# BSPD_-.net
KiCad netlist of a schematic drawn in EasyEDA Pro
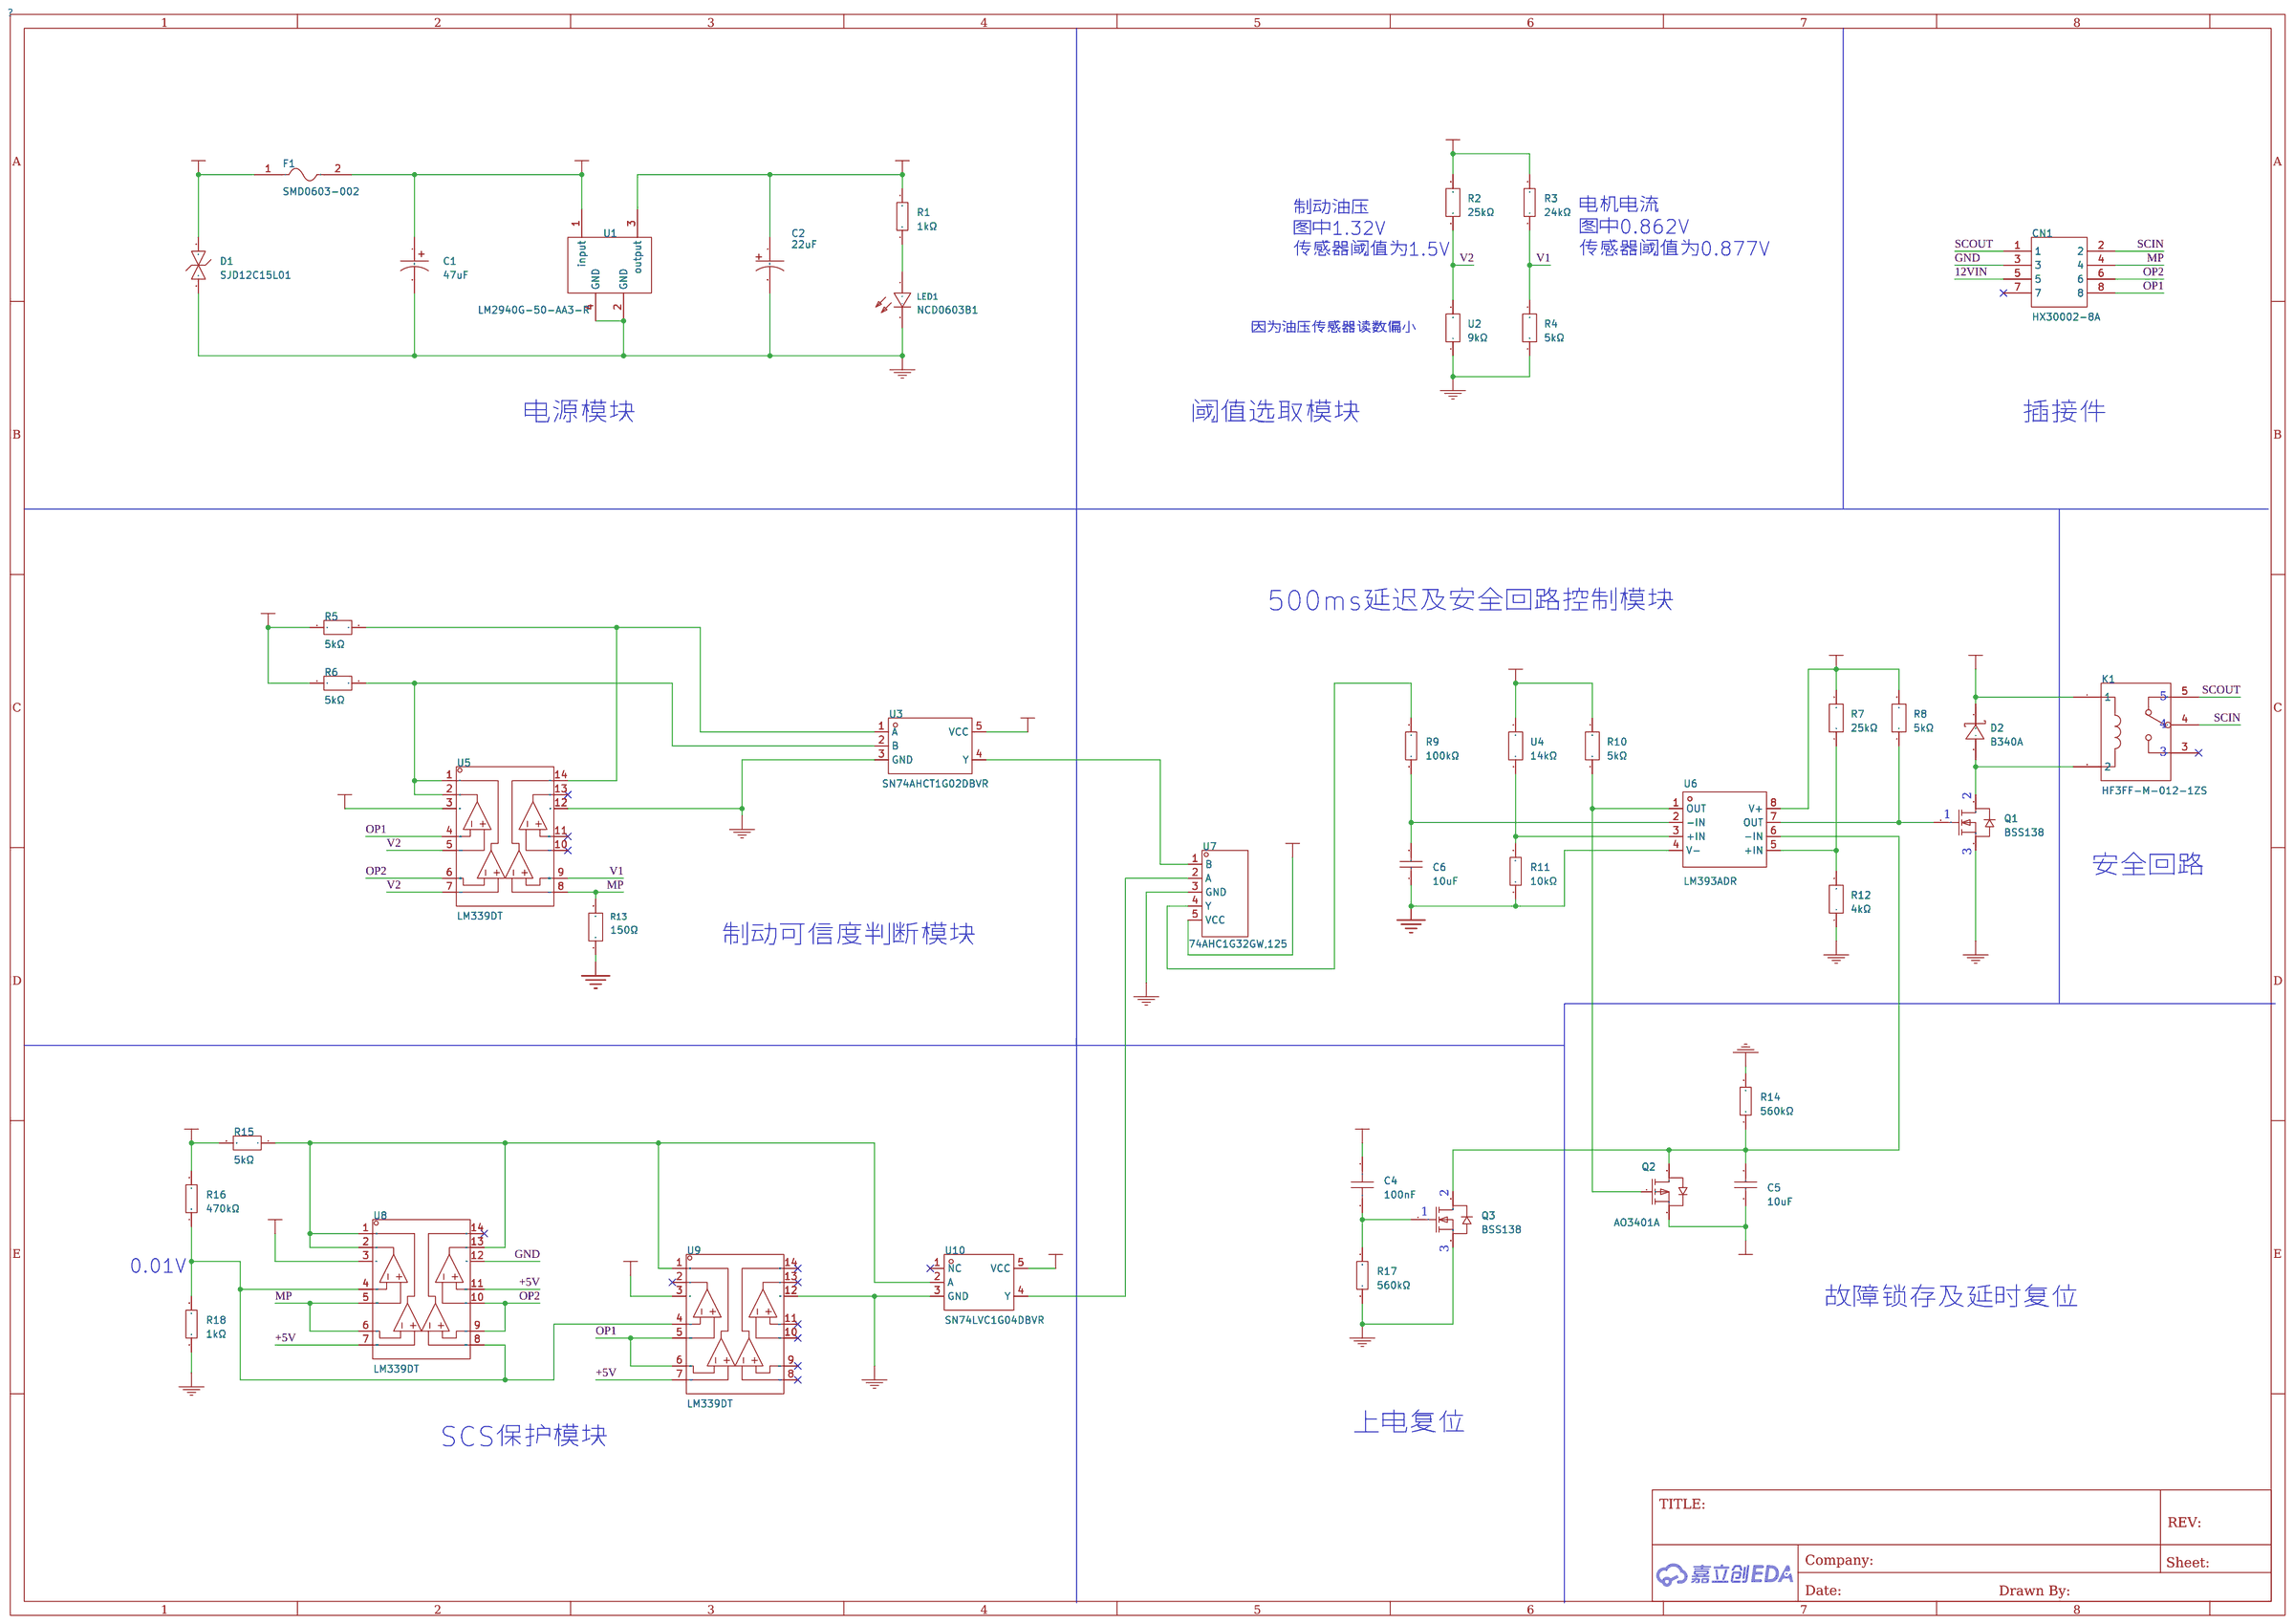
[diagram p0: schematic sheet]

(export (version "E")
  (design (tool "Eeschema 10.0.6"))
  (components
    (comp (ref "C1")
      (value "47uF")
      (footprint "easyedapro:CAP-SMD_BD8.0-L8.3-W8.3-FD")
      (description "容值:47uF;精度:±20%;额定电压:63V;")
      (fields (field (name "Manufacturer Part") "HBW470M1JTR-0810") (field (name "Manufacturer") "lelon(立隆)"))
      (libsource (lib "easyedapro") (part "HBW470M1JTR-0810"))
    )
    (comp (ref "C2")
      (value "22uF")
      (footprint "easyedapro:CAP-SMD_BD6.3-L6.6-W6.6-FD")
      (fields (field (name "Manufacturer Part") "EEHZA1J220XP") (field (name "Manufacturer") "PANASONIC(松下)"))
      (libsource (lib "easyedapro") (part "EEHZA1J220XP"))
    )
    (comp (ref "C4")
      (value "100nF")
      (footprint "easyedapro:C0603")
      (description "容值:100nF;精度:±10%;额定电压:50V;材质(温度系数):X7R;")
      (fields
        (field (name "Manufacturer Part") "CC0603KRX7R9BB104")
        (field (name "Manufacturer") "YAGEO(国巨)")
      )
      (libsource (lib "easyedapro") (part "CC0603KRX7R9BB104"))
    )
    (comp (ref "C5")
      (value "10uF")
      (footprint "easyedapro:C0805")
      (description "容值:10uF;精度:±10%;额定电压:25V;材质(温度系数):X5R;")
      (fields
        (field (name "Manufacturer Part") "CL21A106KAYNNNE")
        (field (name "Manufacturer") "SAMSUNG(三星)")
      )
      (libsource (lib "easyedapro") (part "CL21A106KAYNNNE"))
    )
    (comp (ref "C6")
      (value "10uF")
      (footprint "easyedapro:C0805")
      (description "容值:10uF;精度:±10%;额定电压:25V;材质(温度系数):X5R;")
      (fields
        (field (name "Manufacturer Part") "CL21A106KAYNNNE")
        (field (name "Manufacturer") "SAMSUNG(三星)")
      )
      (libsource (lib "easyedapro") (part "CL21A106KAYNNNE"))
    )
    (comp (ref "CN1")
      (value "HX30002-8A")
      (footprint "easyedapro:CONN-TH_30002-8A-T1P")
      (description "参考系列:-;间距:3mm;插针结构:2x4P;排数:2;每排PIN数:4;行距:3mm;安装方式:-;触头材质:黄铜;")
      (fields (field (name "Manufacturer") "HX(红星)"))
      (libsource (lib "easyedapro") (part "30002-8A-T1P"))
    )
    (comp (ref "D1")
      (value "SJD12C15L01")
      (footprint "easyedapro:SOD-123_L2.7-W1.6-LS3.7-BI")
      (description "反向截止电压(Vrwm):15V;击穿电压(VBR):16.7V;峰值脉冲电流(Ipp)@8/20us:8.2A;钳位电压(Vc)@Ipp:24.4V;")
      (fields (field (name "Manufacturer") "Brightking(君耀电子)"))
      (libsource (lib "easyedapro") (part "SJD12C15L01"))
    )
    (comp (ref "D2")
      (value "B340A")
      (footprint "easyedapro:SMA_L4.3-W2.6-LS5.1-RD")
      (description "直流反向耐压(Vr):40V;平均整流电流(Io):3A;正向压降(Vf):550mV@3A;")
      (fields (field (name "Manufacturer") "MDD"))
      (libsource (lib "easyedapro") (part "B340A"))
    )
    (comp (ref "F1")
      (value "SMD0603-002")
      (footprint "easyedapro:F0603")
      (description "30V,0.02A")
      (fields (field (name "Manufacturer") "台湾陆海"))
      (libsource (lib "easyedapro") (part "SMD0603-002"))
    )
    (comp (ref "K1")
      (value "HF3FF-M-012-1ZS")
      (footprint "easyedapro:RELAY-TH_HF3FF-XX-1ZXX-XXX")
      (description "引脚数:5;线圈电压:12V;触点形式:一组转换:1C(单刀双掷-转换);触点容量(电阻负载):-;触点材料:AgSnO2;")
      (fields (field (name "Manufacturer") "HF(宏发)"))
      (libsource (lib "easyedapro") (part "HF3FF-M-012-1ZS"))
    )
    (comp (ref "LED1")
      (value "NCD0603B1")
      (footprint "easyedapro:LED0603-RD")
      (description "发光颜色:蓝灯;")
      (fields (field (name "Manufacturer") "国星光电"))
      (libsource (lib "easyedapro") (part "FC-DA1608BK-470H10"))
    )
    (comp (ref "Q1")
      (value "BSS138")
      (footprint "easyedapro:SOT-23-3_L2.9-W1.3-P1.90-LS2.4-BR")
      (description "类型:N沟道;漏源电压(Vdss):50V;连续漏极电流(Id):220mA;功率(Pd):360mW;导通电阻(RDS(on)@Vgs,Id):3.5Ω@10V,220mA;")
      (fields (field (name "Manufacturer") "CJ(江苏长电/长晶)"))
      (libsource (lib "easyedapro") (part "BSS138"))
    )
    (comp (ref "Q2")
      (value "AO3401A")
      (footprint "easyedapro:SOT-23_L2.9-W1.3-P1.90-LS2.4-BR")
      (fields (field (name "Manufacturer") "UMW(广东友台半导体)"))
      (libsource (lib "easyedapro") (part "AO3401A_C347476"))
    )
    (comp (ref "Q3")
      (value "BSS138")
      (footprint "easyedapro:SOT-23-3_L2.9-W1.3-P1.90-LS2.4-BR")
      (description "类型:N沟道;漏源电压(Vdss):50V;连续漏极电流(Id):220mA;功率(Pd):360mW;导通电阻(RDS(on)@Vgs,Id):3.5Ω@10V,220mA;")
      (fields (field (name "Manufacturer") "CJ(江苏长电/长晶)"))
      (libsource (lib "easyedapro") (part "BSS138"))
    )
    (comp (ref "R1")
      (value "1kΩ")
      (footprint "easyedapro:R0603")
      (description "电阻类型:厚膜电阻;阻值:1kΩ;精度:±1%;功率:100mW;")
      (fields
        (field (name "Manufacturer Part") "0603WAF1001T5E")
        (field (name "Manufacturer") "UNI-ROYAL(厚声)")
      )
      (libsource (lib "easyedapro") (part "0603WAF1001T5E"))
    )
    (comp (ref "R2")
      (value "25kΩ")
      (footprint "easyedapro:R0603")
      (description "电阻类型:薄膜电阻;阻值:25kΩ;精度:±0.1%;功率:100mW;")
      (fields (field (name "Manufacturer Part") "AR03BTCX2502") (field (name "Manufacturer") "Viking(光颉)"))
      (libsource (lib "easyedapro") (part "AR03BTCX2502"))
    )
    (comp (ref "R3")
      (value "24kΩ")
      (footprint "easyedapro:R0603")
      (description "电阻类型:厚膜电阻;阻值:24kΩ;精度:±1%;功率:100mW;温度系数:±100ppm/°C;")
      (fields
        (field (name "Manufacturer Part") "0603WAF2402T5E")
        (field (name "Manufacturer") "UNI-ROYAL(厚声)")
      )
      (libsource (lib "easyedapro") (part "0603WAF2402T5E"))
    )
    (comp (ref "R4")
      (value "5kΩ")
      (footprint "easyedapro:R0603")
      (description "电阻类型:薄膜电阻;阻值:5kΩ;精度:±0.1%;功率:100mW;")
      (fields (field (name "Manufacturer Part") "AR03BTCX5001") (field (name "Manufacturer") "Viking(光颉)"))
      (libsource (lib "easyedapro") (part "AR03BTCX5001"))
    )
    (comp (ref "R5")
      (value "5kΩ")
      (footprint "easyedapro:R0603")
      (description "电阻类型:薄膜电阻;阻值:5kΩ;精度:±0.1%;功率:100mW;")
      (fields (field (name "Manufacturer Part") "AR03BTCX5001") (field (name "Manufacturer") "Viking(光颉)"))
      (libsource (lib "easyedapro") (part "AR03BTCX5001"))
    )
    (comp (ref "R6")
      (value "5kΩ")
      (footprint "easyedapro:R0603")
      (description "电阻类型:薄膜电阻;阻值:5kΩ;精度:±0.1%;功率:100mW;")
      (fields (field (name "Manufacturer Part") "AR03BTCX5001") (field (name "Manufacturer") "Viking(光颉)"))
      (libsource (lib "easyedapro") (part "AR03BTCX5001"))
    )
    (comp (ref "R7")
      (value "25kΩ")
      (footprint "easyedapro:R0603")
      (description "电阻类型:薄膜电阻;阻值:25kΩ;精度:±0.1%;功率:100mW;")
      (fields (field (name "Manufacturer Part") "AR03BTCX2502") (field (name "Manufacturer") "Viking(光颉)"))
      (libsource (lib "easyedapro") (part "AR03BTCX2502"))
    )
    (comp (ref "R8")
      (value "5kΩ")
      (footprint "easyedapro:R0603")
      (description "电阻类型:薄膜电阻;阻值:5kΩ;精度:±0.1%;功率:100mW;")
      (fields (field (name "Manufacturer Part") "AR03BTCX5001") (field (name "Manufacturer") "Viking(光颉)"))
      (libsource (lib "easyedapro") (part "AR03BTCX5001"))
    )
    (comp (ref "R9")
      (value "100kΩ")
      (footprint "easyedapro:R0603")
      (description "电阻类型:厚膜电阻;阻值:100kΩ;精度:±1%;功率:100mW;")
      (fields
        (field (name "Manufacturer Part") "0603WAF1003T5E")
        (field (name "Manufacturer") "UNI-ROYAL(厚声)")
      )
      (libsource (lib "easyedapro") (part "0603WAF1003T5E"))
    )
    (comp (ref "R10")
      (value "5kΩ")
      (footprint "easyedapro:R0603")
      (description "电阻类型:薄膜电阻;阻值:5kΩ;精度:±0.1%;功率:100mW;")
      (fields (field (name "Manufacturer Part") "AR03BTCX5001") (field (name "Manufacturer") "Viking(光颉)"))
      (libsource (lib "easyedapro") (part "AR03BTCX5001"))
    )
    (comp (ref "R11")
      (value "10kΩ")
      (footprint "easyedapro:R0603")
      (description "电阻类型:厚膜电阻;阻值:10kΩ;精度:±1%;功率:100mW;")
      (fields
        (field (name "Manufacturer Part") "0603WAF1002T5E")
        (field (name "Manufacturer") "UNI-ROYAL(厚声)")
      )
      (libsource (lib "easyedapro") (part "0603WAF1002T5E"))
    )
    (comp (ref "R12")
      (value "4kΩ")
      (footprint "easyedapro:R0805")
      (description "电阻类型:薄膜电阻;阻值:4kΩ;精度:±1%;功率:125mW;")
      (fields (field (name "Manufacturer Part") "ARG05FTC4001N") (field (name "Manufacturer") "Viking(光颉)"))
      (libsource (lib "easyedapro") (part "ARG05FTC4001N"))
    )
    (comp (ref "R13")
      (value "150Ω")
      (footprint "easyedapro:R0603")
      (description "电阻类型:薄膜电阻;阻值:150Ω;精度:±0.1%;功率:100mW;温度系数:±10ppm/°C;")
      (fields (field (name "Manufacturer Part") "PTFR0603B150RN9") (field (name "Manufacturer") "RESI(开步睿思）"))
      (libsource (lib "easyedapro") (part "PTFR0603B150RN9"))
    )
    (comp (ref "R14")
      (value "560kΩ")
      (footprint "easyedapro:R0603")
      (description "电阻类型:厚膜电阻;阻值:560kΩ;精度:±1%;功率:100mW;")
      (fields
        (field (name "Manufacturer Part") "0603WAF5603T5E")
        (field (name "Manufacturer") "UNI-ROYAL(厚声)")
      )
      (libsource (lib "easyedapro") (part "0603WAF5603T5E"))
    )
    (comp (ref "R15")
      (value "5kΩ")
      (footprint "easyedapro:R0603")
      (description "电阻类型:薄膜电阻;阻值:5kΩ;精度:±0.1%;功率:100mW;")
      (fields (field (name "Manufacturer Part") "AR03BTCX5001") (field (name "Manufacturer") "Viking(光颉)"))
      (libsource (lib "easyedapro") (part "AR03BTCX5001"))
    )
    (comp (ref "R16")
      (value "470kΩ")
      (footprint "easyedapro:R0603")
      (description "电阻类型:厚膜电阻;阻值:470kΩ;精度:±1%;功率:100mW;")
      (fields
        (field (name "Manufacturer Part") "0603WAF4703T5E")
        (field (name "Manufacturer") "UNI-ROYAL(厚声)")
      )
      (libsource (lib "easyedapro") (part "0603WAF4703T5E"))
    )
    (comp (ref "R17")
      (value "560kΩ")
      (footprint "easyedapro:R0603")
      (description "电阻类型:厚膜电阻;阻值:560kΩ;精度:±1%;功率:100mW;")
      (fields
        (field (name "Manufacturer Part") "0603WAF5603T5E")
        (field (name "Manufacturer") "UNI-ROYAL(厚声)")
      )
      (libsource (lib "easyedapro") (part "0603WAF5603T5E"))
    )
    (comp (ref "R18")
      (value "1kΩ")
      (footprint "easyedapro:R0603")
      (description "电阻类型:厚膜电阻;阻值:1kΩ;精度:±1%;功率:100mW;")
      (fields
        (field (name "Manufacturer Part") "0603WAF1001T5E")
        (field (name "Manufacturer") "UNI-ROYAL(厚声)")
      )
      (libsource (lib "easyedapro") (part "0603WAF1001T5E"))
    )
    (comp (ref "U1")
      (value "LM2940G-50-AA3-R")
      (footprint "easyedapro:SOT-223-4_L6.5-W3.5-P2.30-LS7.0-BR")
      (description "输出类型:固定;输出极性:正;输出通道数:1;最大输入电压:26V;输出电压:5V;压差:800mV@(1A);输出电流:1A;电源纹波抑制比(PSRR):72dB@(120Hz);")
      (fields (field (name "Manufacturer") "UTC(友顺)"))
      (libsource (lib "easyedapro") (part "LM2940G-50-AA3-R"))
    )
    (comp (ref "U2")
      (value "9kΩ")
      (footprint "easyedapro:R0805")
      (description "电阻类型:薄膜电阻;阻值:9kΩ;精度:±0.1%;功率:125mW;")
      (fields (field (name "Manufacturer Part") "ARG05BTC9001N") (field (name "Manufacturer") "Viking(光颉)"))
      (libsource (lib "easyedapro") (part "ARG05BTC9001N"))
    )
    (comp (ref "U3")
      (value "SN74AHCT1G02DBVR")
      (footprint "easyedapro:SOT-23-5_L3.0-W1.7-P0.95-LS2.8-BR")
      (description "逻辑电路的归属系列:74AHCT;逻辑类型:或非门;")
      (fields (field (name "Manufacturer") "TI(德州仪器)"))
      (libsource (lib "easyedapro") (part "SN74AHCT1G02DBVR"))
    )
    (comp (ref "U4")
      (value "14kΩ")
      (footprint "easyedapro:R0402")
      (description "阻值:14kΩ;精度:±1%;")
      (fields (field (name "Manufacturer Part") "SCR0402F14K") (field (name "Manufacturer") "VO(翔胜)"))
      (libsource (lib "easyedapro") (part "SCR0402F14K"))
    )
    (comp (ref "U5")
      (value "LM339DT")
      (footprint "easyedapro:SOIC-14_L8.7-W3.9-P1.27-LS6.0-BL")
      (fields (field (name "Manufacturer") "ST(意法半导体)"))
      (libsource (lib "easyedapro") (part "LM339DT"))
    )
    (comp (ref "U6")
      (value "LM393ADR")
      (footprint "easyedapro:SOIC-8_L5.0-W4.0-P1.27-LS6.0-BL")
      (description "比较器组数:2;电源电压:2V~36V,±1V~18V;各通道供电电流:2.5mA;输出类型:CMOS, MOS, Open-Collector, TTL;传播延迟:-;")
      (fields (field (name "Manufacturer") "TI(德州仪器)"))
      (libsource (lib "easyedapro") (part "LM393ADR"))
    )
    (comp (ref "U7")
      (value "74AHC1G32GW,125")
      (footprint "easyedapro:SOT-353-5_L2.0-W1.3-P0.65-LS2.1-BR")
      (description "逻辑类型:或门;通道数:1;电源电压:2V~5.5V;静态电流(最大值):1uA;最大传播延迟:7.5ns@5V,50pF;")
      (fields (field (name "Manufacturer") "Nexperia(安世)"))
      (libsource (lib "easyedapro") (part "74AHC1G32GW,125"))
    )
    (comp (ref "U8")
      (value "LM339DT")
      (footprint "easyedapro:SOIC-14_L8.7-W3.9-P1.27-LS6.0-BL")
      (fields (field (name "Manufacturer") "ST(意法半导体)"))
      (libsource (lib "easyedapro") (part "LM339DT"))
    )
    (comp (ref "U9")
      (value "LM339DT")
      (footprint "easyedapro:SOIC-14_L8.7-W3.9-P1.27-LS6.0-BL")
      (fields (field (name "Manufacturer") "ST(意法半导体)"))
      (libsource (lib "easyedapro") (part "LM339DT"))
    )
    (comp (ref "U10")
      (value "SN74LVC1G04DBVR")
      (footprint "easyedapro:SOT-23-5_L3.0-W1.7-P0.95-LS2.8-BR")
      (fields (field (name "Manufacturer") "UMW(广东友台半导体)"))
      (libsource (lib "easyedapro") (part "SN74LVC1G04DBVR_C434067"))
    )
  )
  (nets
    (net (code "1") (name "+5V") (class "Default")
      (node (ref "C2") (pin "1") (pinfunction "1_1") (pintype "input"))
      (node (ref "C4") (pin "2") (pinfunction "2_2") (pintype "input"))
      (node (ref "C5") (pin "1") (pinfunction "1_1") (pintype "input"))
      (node (ref "Q2") (pin "2") (pinfunction "S_2") (pintype "input"))
      (node (ref "R1") (pin "2") (pinfunction "2_2") (pintype "input"))
      (node (ref "R10") (pin "2") (pinfunction "2_2") (pintype "input"))
      (node (ref "R15") (pin "2") (pinfunction "2_2") (pintype "input"))
      (node (ref "R16") (pin "2") (pinfunction "2_2") (pintype "input"))
      (node (ref "R2") (pin "2") (pinfunction "2_2") (pintype "input"))
      (node (ref "R3") (pin "2") (pinfunction "2_2") (pintype "input"))
      (node (ref "R5") (pin "2") (pinfunction "2_2") (pintype "input"))
      (node (ref "R6") (pin "2") (pinfunction "2_2") (pintype "input"))
      (node (ref "R7") (pin "2") (pinfunction "2_2") (pintype "input"))
      (node (ref "R8") (pin "2") (pinfunction "2_2") (pintype "input"))
      (node (ref "U1") (pin "3") (pinfunction "output_3") (pintype "input"))
      (node (ref "U10") (pin "5") (pinfunction "VCC_5") (pintype "input"))
      (node (ref "U3") (pin "5") (pinfunction "VCC_5") (pintype "input"))
      (node (ref "U4") (pin "2") (pinfunction "2_2") (pintype "input"))
      (node (ref "U5") (pin "3") (pinfunction "VDD_3") (pintype "input"))
      (node (ref "U6") (pin "8") (pinfunction "V+_8") (pintype "input"))
      (node (ref "U7") (pin "5") (pinfunction "VCC_5") (pintype "input"))
      (node (ref "U8") (pin "11") (pinfunction "Non-inverting_input4_11") (pintype "input"))
      (node (ref "U8") (pin "3") (pinfunction "VDD_3") (pintype "input"))
      (node (ref "U8") (pin "7") (pinfunction "Non-inverting_input2_7") (pintype "input"))
      (node (ref "U9") (pin "3") (pinfunction "VDD_3") (pintype "input"))
      (node (ref "U9") (pin "7") (pinfunction "Non-inverting_input2_7") (pintype "input"))
    )
    (net (code "2") (name "+12V") (class "Default")
      (node (ref "C1") (pin "1") (pinfunction "1_1") (pintype "input"))
      (node (ref "D2") (pin "1") (pinfunction "K_1") (pintype "input"))
      (node (ref "F1") (pin "2") (pinfunction "2_2") (pintype "input"))
      (node (ref "K1") (pin "1") (pinfunction "1_1") (pintype "input"))
      (node (ref "U1") (pin "1") (pinfunction "input_1") (pintype "input"))
    )
    (net (code "3") (name "/MP") (class "Default")
      (node (ref "CN1") (pin "4") (pinfunction "4_4") (pintype "input"))
      (node (ref "R13") (pin "2") (pinfunction "2_2") (pintype "input"))
      (node (ref "U5") (pin "8") (pinfunction "Inverting_input3_8") (pintype "input"))
      (node (ref "U8") (pin "5") (pinfunction "Non-inverting_input1_5") (pintype "input"))
      (node (ref "U8") (pin "6") (pinfunction "Inverting_input2_6") (pintype "input"))
    )
    (net (code "4") (name "/OP1") (class "Default")
      (node (ref "CN1") (pin "8") (pinfunction "8_8") (pintype "input"))
      (node (ref "U5") (pin "4") (pinfunction "Inverting_input1_4") (pintype "input"))
      (node (ref "U9") (pin "5") (pinfunction "Non-inverting_input1_5") (pintype "input"))
      (node (ref "U9") (pin "6") (pinfunction "Inverting_input2_6") (pintype "input"))
    )
    (net (code "5") (name "/OP2") (class "Default")
      (node (ref "CN1") (pin "6") (pinfunction "6_6") (pintype "input"))
      (node (ref "U5") (pin "6") (pinfunction "Inverting_input2_6") (pintype "input"))
      (node (ref "U8") (pin "10") (pinfunction "Inverting_input4_10") (pintype "input"))
      (node (ref "U8") (pin "9") (pinfunction "Non-inverting_input3_9") (pintype "input"))
    )
    (net (code "6") (name "/SCIN") (class "Default")
      (node (ref "CN1") (pin "2") (pinfunction "2_2") (pintype "input"))
      (node (ref "K1") (pin "4") (pinfunction "4_4") (pintype "input"))
    )
    (net (code "7") (name "/SCOUT") (class "Default")
      (node (ref "CN1") (pin "1") (pinfunction "1_1") (pintype "input"))
      (node (ref "K1") (pin "5") (pinfunction "5_5") (pintype "input"))
    )
    (net (code "8") (name "/V1") (class "Default")
      (node (ref "R3") (pin "1") (pinfunction "1_1") (pintype "input"))
      (node (ref "R4") (pin "1") (pinfunction "1_1") (pintype "input"))
      (node (ref "U5") (pin "9") (pinfunction "Non-inverting_input3_9") (pintype "input"))
    )
    (net (code "9") (name "/V2") (class "Default")
      (node (ref "R2") (pin "1") (pinfunction "1_1") (pintype "input"))
      (node (ref "U2") (pin "2") (pinfunction "2_2") (pintype "input"))
      (node (ref "U5") (pin "5") (pinfunction "Non-inverting_input1_5") (pintype "input"))
      (node (ref "U5") (pin "7") (pinfunction "Non-inverting_input2_7") (pintype "input"))
    )
    (net (code "10") (name "12VIN") (class "Default")
      (node (ref "CN1") (pin "5") (pinfunction "5_5") (pintype "input"))
      (node (ref "D1") (pin "2") (pinfunction "2_2") (pintype "input"))
      (node (ref "F1") (pin "1") (pinfunction "1_1") (pintype "input"))
    )
    (net (code "11") (name "GND") (class "Default")
      (node (ref "C1") (pin "2") (pinfunction "2_2") (pintype "input"))
      (node (ref "C2") (pin "2") (pinfunction "2_2") (pintype "input"))
      (node (ref "C6") (pin "1") (pinfunction "1_1") (pintype "input"))
      (node (ref "CN1") (pin "3") (pinfunction "3_3") (pintype "input"))
      (node (ref "D1") (pin "1") (pinfunction "1_1") (pintype "input"))
      (node (ref "LED1") (pin "1") (pinfunction "-_1") (pintype "input"))
      (node (ref "Q1") (pin "2") (pinfunction "S_2") (pintype "input"))
      (node (ref "Q3") (pin "2") (pinfunction "S_2") (pintype "input"))
      (node (ref "R11") (pin "1") (pinfunction "1_1") (pintype "input"))
      (node (ref "R12") (pin "1") (pinfunction "1_1") (pintype "input"))
      (node (ref "R13") (pin "1") (pinfunction "1_1") (pintype "input"))
      (node (ref "R14") (pin "2") (pinfunction "2_2") (pintype "input"))
      (node (ref "R17") (pin "1") (pinfunction "1_1") (pintype "input"))
      (node (ref "R18") (pin "1") (pinfunction "1_1") (pintype "input"))
      (node (ref "R4") (pin "2") (pinfunction "2_2") (pintype "input"))
      (node (ref "U1") (pin "2") (pinfunction "GND_2") (pintype "input"))
      (node (ref "U1") (pin "4") (pinfunction "GND_4") (pintype "input"))
      (node (ref "U10") (pin "3") (pinfunction "GND_3") (pintype "input"))
      (node (ref "U2") (pin "1") (pinfunction "1_1") (pintype "input"))
      (node (ref "U3") (pin "3") (pinfunction "GND_3") (pintype "input"))
      (node (ref "U5") (pin "12") (pinfunction "GND_12") (pintype "input"))
      (node (ref "U6") (pin "4") (pinfunction "V-_4") (pintype "input"))
      (node (ref "U7") (pin "3") (pinfunction "GND_3") (pintype "input"))
      (node (ref "U8") (pin "12") (pinfunction "GND_12") (pintype "input"))
      (node (ref "U9") (pin "12") (pinfunction "GND_12") (pintype "input"))
    )
    (net (code "12") (name "Net-(C6-Pad2)") (class "Default")
      (node (ref "C6") (pin "2") (pinfunction "2_2") (pintype "input"))
      (node (ref "R9") (pin "1") (pinfunction "1_1") (pintype "input"))
      (node (ref "U6") (pin "2") (pinfunction "-IN_2") (pintype "input"))
    )
    (net (code "13") (name "Net-(D2-A)") (class "Default")
      (node (ref "D2") (pin "2") (pinfunction "A_2") (pintype "input"))
      (node (ref "K1") (pin "2") (pinfunction "2_2") (pintype "input"))
      (node (ref "Q1") (pin "3") (pinfunction "D_3") (pintype "input"))
    )
    (net (code "14") (name "Net-(LED1-+)") (class "Default")
      (node (ref "LED1") (pin "2") (pinfunction "+_2") (pintype "input"))
      (node (ref "R1") (pin "1") (pinfunction "1_1") (pintype "input"))
    )
    (net (code "15") (name "Net-(Q1-G)") (class "Default")
      (node (ref "Q1") (pin "1") (pinfunction "G_1") (pintype "input"))
      (node (ref "R8") (pin "1") (pinfunction "1_1") (pintype "input"))
      (node (ref "U6") (pin "7") (pinfunction "OUT_7") (pintype "input"))
    )
    (net (code "16") (name "Net-(Q2-D)") (class "Default")
      (node (ref "C5") (pin "2") (pinfunction "2_2") (pintype "input"))
      (node (ref "Q2") (pin "3") (pinfunction "D_3") (pintype "input"))
      (node (ref "Q3") (pin "3") (pinfunction "D_3") (pintype "input"))
      (node (ref "R14") (pin "1") (pinfunction "1_1") (pintype "input"))
      (node (ref "U6") (pin "6") (pinfunction "-IN_6") (pintype "input"))
    )
    (net (code "17") (name "Net-(Q2-G)") (class "Default")
      (node (ref "Q2") (pin "1") (pinfunction "G_1") (pintype "input"))
      (node (ref "R10") (pin "1") (pinfunction "1_1") (pintype "input"))
      (node (ref "U6") (pin "1") (pinfunction "OUT_1") (pintype "input"))
    )
    (net (code "18") (name "Net-(Q3-G)") (class "Default")
      (node (ref "C4") (pin "1") (pinfunction "1_1") (pintype "input"))
      (node (ref "Q3") (pin "1") (pinfunction "G_1") (pintype "input"))
      (node (ref "R17") (pin "2") (pinfunction "2_2") (pintype "input"))
    )
    (net (code "19") (name "Net-(R11-Pad2)") (class "Default")
      (node (ref "R11") (pin "2") (pinfunction "2_2") (pintype "input"))
      (node (ref "U4") (pin "1") (pinfunction "1_1") (pintype "input"))
      (node (ref "U6") (pin "3") (pinfunction "+IN_3") (pintype "input"))
    )
    (net (code "20") (name "Net-(R12-Pad2)") (class "Default")
      (node (ref "R12") (pin "2") (pinfunction "2_2") (pintype "input"))
      (node (ref "R7") (pin "1") (pinfunction "1_1") (pintype "input"))
      (node (ref "U6") (pin "5") (pinfunction "+IN_5") (pintype "input"))
    )
    (net (code "21") (name "Net-(U3-A)") (class "Default")
      (node (ref "R5") (pin "1") (pinfunction "1_1") (pintype "input"))
      (node (ref "U3") (pin "1") (pinfunction "A_1") (pintype "input"))
      (node (ref "U5") (pin "14") (pinfunction "OUTPUT3_14") (pintype "input"))
    )
    (net (code "22") (name "Net-(U3-B)") (class "Default")
      (node (ref "R6") (pin "1") (pinfunction "1_1") (pintype "input"))
      (node (ref "U3") (pin "2") (pinfunction "B_2") (pintype "input"))
      (node (ref "U5") (pin "1") (pinfunction "OUTPUT2_1") (pintype "input"))
      (node (ref "U5") (pin "2") (pinfunction "OUTPUT1_2") (pintype "input"))
    )
    (net (code "23") (name "Net-(U3-Y)") (class "Default")
      (node (ref "U3") (pin "4") (pinfunction "Y_4") (pintype "input"))
      (node (ref "U7") (pin "1") (pinfunction "B_1") (pintype "input"))
    )
    (net (code "24") (name "Net-(U7-Y)") (class "Default")
      (node (ref "R9") (pin "2") (pinfunction "2_2") (pintype "input"))
      (node (ref "U7") (pin "4") (pinfunction "Y_4") (pintype "input"))
    )
    (net (code "25") (name "Net-(U8-Inverting_input1)") (class "Default")
      (node (ref "R16") (pin "1") (pinfunction "1_1") (pintype "input"))
      (node (ref "R18") (pin "2") (pinfunction "2_2") (pintype "input"))
      (node (ref "U8") (pin "4") (pinfunction "Inverting_input1_4") (pintype "input"))
      (node (ref "U8") (pin "8") (pinfunction "Inverting_input3_8") (pintype "input"))
      (node (ref "U9") (pin "4") (pinfunction "Inverting_input1_4") (pintype "input"))
    )
    (net (code "26") (name "Net-(U10-A)") (class "Default")
      (node (ref "R15") (pin "1") (pinfunction "1_1") (pintype "input"))
      (node (ref "U10") (pin "2") (pinfunction "A_2") (pintype "input"))
      (node (ref "U8") (pin "1") (pinfunction "OUTPUT2_1") (pintype "input"))
      (node (ref "U8") (pin "13") (pinfunction "OUTPUT4_13") (pintype "input"))
      (node (ref "U8") (pin "2") (pinfunction "OUTPUT1_2") (pintype "input"))
      (node (ref "U9") (pin "1") (pinfunction "OUTPUT2_1") (pintype "input"))
    )
    (net (code "27") (name "Net-(U10-Y)") (class "Default")
      (node (ref "U10") (pin "4") (pinfunction "Y_4") (pintype "input"))
      (node (ref "U7") (pin "2") (pinfunction "A_2") (pintype "input"))
    )
    (net (code "28") (name "unconnected-(CN1-Pad7)") (class "Default")
      (node (ref "CN1") (pin "7") (pinfunction "7_7") (pintype "input+no_connect"))
    )
    (net (code "29") (name "unconnected-(K1-Pad3)") (class "Default")
      (node (ref "K1") (pin "3") (pinfunction "3_3") (pintype "input+no_connect"))
    )
    (net (code "30") (name "unconnected-(U5-Inverting_input4-Pad10)") (class "Default")
      (node (ref "U5") (pin "10") (pinfunction "Inverting_input4_10") (pintype "input+no_connect"))
    )
    (net (code "31") (name "unconnected-(U5-Non-inverting_input4-Pad11)") (class "Default")
      (node (ref "U5") (pin "11") (pinfunction "Non-inverting_input4_11") (pintype "input+no_connect"))
    )
    (net (code "32") (name "unconnected-(U5-OUTPUT4-Pad13)") (class "Default")
      (node (ref "U5") (pin "13") (pinfunction "OUTPUT4_13") (pintype "input+no_connect"))
    )
    (net (code "33") (name "unconnected-(U8-OUTPUT3-Pad14)") (class "Default")
      (node (ref "U8") (pin "14") (pinfunction "OUTPUT3_14") (pintype "input+no_connect"))
    )
    (net (code "34") (name "unconnected-(U9-Inverting_input3-Pad8)") (class "Default")
      (node (ref "U9") (pin "8") (pinfunction "Inverting_input3_8") (pintype "input+no_connect"))
    )
    (net (code "35") (name "unconnected-(U9-Inverting_input4-Pad10)") (class "Default")
      (node (ref "U9") (pin "10") (pinfunction "Inverting_input4_10") (pintype "input+no_connect"))
    )
    (net (code "36") (name "unconnected-(U9-Non-inverting_input3-Pad9)") (class "Default")
      (node (ref "U9") (pin "9") (pinfunction "Non-inverting_input3_9") (pintype "input+no_connect"))
    )
    (net (code "37") (name "unconnected-(U9-Non-inverting_input4-Pad11)") (class "Default")
      (node (ref "U9") (pin "11") (pinfunction "Non-inverting_input4_11") (pintype "input+no_connect"))
    )
    (net (code "38") (name "unconnected-(U9-OUTPUT1-Pad2)") (class "Default")
      (node (ref "U9") (pin "2") (pinfunction "OUTPUT1_2") (pintype "input+no_connect"))
    )
    (net (code "39") (name "unconnected-(U9-OUTPUT3-Pad14)") (class "Default")
      (node (ref "U9") (pin "14") (pinfunction "OUTPUT3_14") (pintype "input+no_connect"))
    )
    (net (code "40") (name "unconnected-(U9-OUTPUT4-Pad13)") (class "Default")
      (node (ref "U9") (pin "13") (pinfunction "OUTPUT4_13") (pintype "input+no_connect"))
    )
    (net (code "41") (name "unconnected-(U10-NC-Pad1)") (class "Default")
      (node (ref "U10") (pin "1") (pinfunction "NC_1") (pintype "input+no_connect"))
    )
  )
)
